# battery.net
KiCad netlist of a schematic drawn in Altium Designer
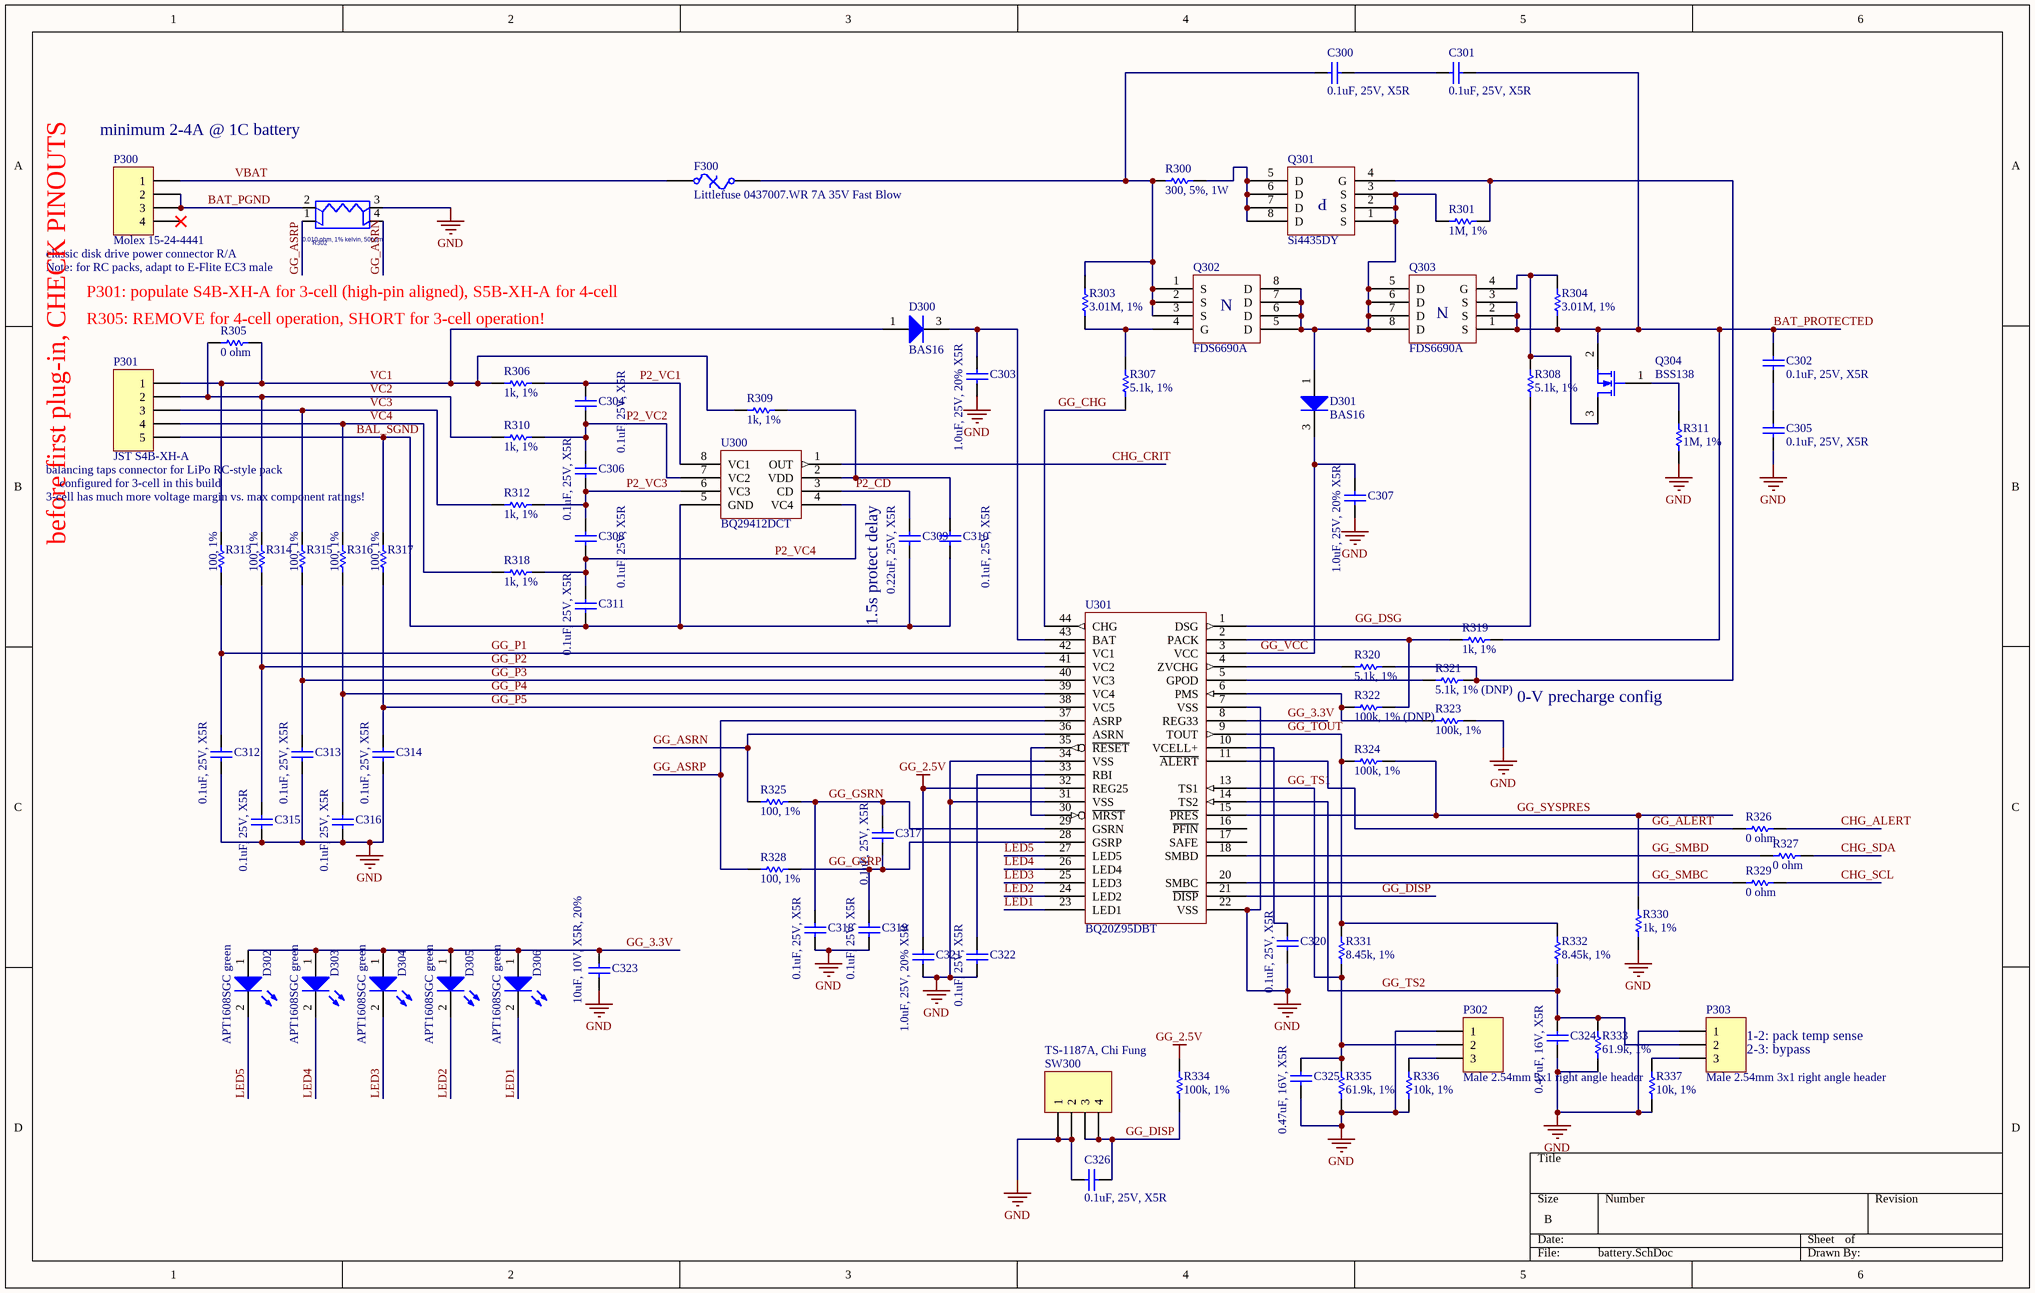
[diagram p0: battery.SchDoc]

(export (version "E")
  (design (tool "Eeschema 10.0.6"))
  (components
    (comp (ref "C300")
      (value "0.1uF, 25V, X5R")
      (footprint "CAPC1005N")
      (description "Capacitor (Semiconductor SIM Model)")
      (fields (field (name "PUBLISHER") "Altium Limited"))
      (libsource (lib "Miscellaneous Devices") (part "Cap Semi"))
    )
    (comp (ref "C301")
      (value "0.1uF, 25V, X5R")
      (footprint "CAPC1005N")
      (description "Capacitor (Semiconductor SIM Model)")
      (fields (field (name "PUBLISHER") "Altium Limited"))
      (libsource (lib "Miscellaneous Devices") (part "Cap Semi"))
    )
    (comp (ref "C302")
      (value "0.1uF, 25V, X5R")
      (footprint "CAPC1005N")
      (description "Capacitor (Semiconductor SIM Model)")
      (fields (field (name "PUBLISHER") "Altium Limited"))
      (libsource (lib "Miscellaneous Devices") (part "Cap Semi"))
    )
    (comp (ref "C303")
      (value "1.0uF, 25V, 20% X5R")
      (footprint "CAPC1608N")
      (description "Capacitor (Semiconductor SIM Model)")
      (fields (field (name "PUBLISHER") "Altium Limited"))
      (libsource (lib "Miscellaneous Devices") (part "Cap Semi"))
    )
    (comp (ref "C304")
      (value "0.1uF, 25V, X5R")
      (footprint "CAPC1005N")
      (description "Capacitor (Semiconductor SIM Model)")
      (fields (field (name "PUBLISHER") "Altium Limited"))
      (libsource (lib "Miscellaneous Devices") (part "Cap Semi"))
    )
    (comp (ref "C305")
      (value "0.1uF, 25V, X5R")
      (footprint "CAPC1005N")
      (description "Capacitor (Semiconductor SIM Model)")
      (fields (field (name "PUBLISHER") "Altium Limited"))
      (libsource (lib "Miscellaneous Devices") (part "Cap Semi"))
    )
    (comp (ref "C306")
      (value "0.1uF, 25V, X5R")
      (footprint "CAPC1005N")
      (description "Capacitor (Semiconductor SIM Model)")
      (fields (field (name "PUBLISHER") "Altium Limited"))
      (libsource (lib "Miscellaneous Devices") (part "Cap Semi"))
    )
    (comp (ref "C307")
      (value "1.0uF, 25V, 20% X5R")
      (footprint "CAPC1608N")
      (description "Capacitor (Semiconductor SIM Model)")
      (fields (field (name "PUBLISHER") "Altium Limited"))
      (libsource (lib "Miscellaneous Devices") (part "Cap Semi"))
    )
    (comp (ref "C308")
      (value "0.1uF, 25V, X5R")
      (footprint "CAPC1005N")
      (description "Capacitor (Semiconductor SIM Model)")
      (fields (field (name "PUBLISHER") "Altium Limited"))
      (libsource (lib "Miscellaneous Devices") (part "Cap Semi"))
    )
    (comp (ref "C309")
      (value "0.22uF, 25V, X5R")
      (footprint "CAPC1005N")
      (description "Capacitor (Semiconductor SIM Model)")
      (fields (field (name "PUBLISHER") "Altium Limited"))
      (libsource (lib "Miscellaneous Devices") (part "Cap Semi"))
    )
    (comp (ref "C310")
      (value "0.1uF, 25V, X5R")
      (footprint "CAPC1005N")
      (description "Capacitor (Semiconductor SIM Model)")
      (fields (field (name "PUBLISHER") "Altium Limited"))
      (libsource (lib "Miscellaneous Devices") (part "Cap Semi"))
    )
    (comp (ref "C311")
      (value "0.1uF, 25V, X5R")
      (footprint "CAPC1005N")
      (description "Capacitor (Semiconductor SIM Model)")
      (fields (field (name "PUBLISHER") "Altium Limited"))
      (libsource (lib "Miscellaneous Devices") (part "Cap Semi"))
    )
    (comp (ref "C312")
      (value "0.1uF, 25V, X5R")
      (footprint "CAPC1005N")
      (description "Capacitor (Semiconductor SIM Model)")
      (fields (field (name "PUBLISHER") "Altium Limited"))
      (libsource (lib "Miscellaneous Devices") (part "Cap Semi"))
    )
    (comp (ref "C313")
      (value "0.1uF, 25V, X5R")
      (footprint "CAPC1005N")
      (description "Capacitor (Semiconductor SIM Model)")
      (fields (field (name "PUBLISHER") "Altium Limited"))
      (libsource (lib "Miscellaneous Devices") (part "Cap Semi"))
    )
    (comp (ref "C314")
      (value "0.1uF, 25V, X5R")
      (footprint "CAPC1005N")
      (description "Capacitor (Semiconductor SIM Model)")
      (fields (field (name "PUBLISHER") "Altium Limited"))
      (libsource (lib "Miscellaneous Devices") (part "Cap Semi"))
    )
    (comp (ref "C315")
      (value "0.1uF, 25V, X5R")
      (footprint "CAPC1005N")
      (description "Capacitor (Semiconductor SIM Model)")
      (fields (field (name "PUBLISHER") "Altium Limited"))
      (libsource (lib "Miscellaneous Devices") (part "Cap Semi"))
    )
    (comp (ref "C316")
      (value "0.1uF, 25V, X5R")
      (footprint "CAPC1005N")
      (description "Capacitor (Semiconductor SIM Model)")
      (fields (field (name "PUBLISHER") "Altium Limited"))
      (libsource (lib "Miscellaneous Devices") (part "Cap Semi"))
    )
    (comp (ref "C317")
      (value "0.1uF, 25V, X5R")
      (footprint "CAPC1005N")
      (description "Capacitor (Semiconductor SIM Model)")
      (fields (field (name "PUBLISHER") "Altium Limited"))
      (libsource (lib "Miscellaneous Devices") (part "Cap Semi"))
    )
    (comp (ref "C318")
      (value "0.1uF, 25V, X5R")
      (footprint "CAPC1005N")
      (description "Capacitor (Semiconductor SIM Model)")
      (fields (field (name "PUBLISHER") "Altium Limited"))
      (libsource (lib "Miscellaneous Devices") (part "Cap Semi"))
    )
    (comp (ref "C319")
      (value "0.1uF, 25V, X5R")
      (footprint "CAPC1005N")
      (description "Capacitor (Semiconductor SIM Model)")
      (fields (field (name "PUBLISHER") "Altium Limited"))
      (libsource (lib "Miscellaneous Devices") (part "Cap Semi"))
    )
    (comp (ref "C320")
      (value "0.1uF, 25V, X5R")
      (footprint "CAPC1005N")
      (description "Capacitor (Semiconductor SIM Model)")
      (fields (field (name "PUBLISHER") "Altium Limited"))
      (libsource (lib "Miscellaneous Devices") (part "Cap Semi"))
    )
    (comp (ref "C321")
      (value "1.0uF, 25V, 20% X5R")
      (footprint "CAPC1608N")
      (description "Capacitor (Semiconductor SIM Model)")
      (fields (field (name "PUBLISHER") "Altium Limited"))
      (libsource (lib "Miscellaneous Devices") (part "Cap Semi"))
    )
    (comp (ref "C322")
      (value "0.1uF, 25V, X5R")
      (footprint "CAPC1005N")
      (description "Capacitor (Semiconductor SIM Model)")
      (fields (field (name "PUBLISHER") "Altium Limited"))
      (libsource (lib "Miscellaneous Devices") (part "Cap Semi"))
    )
    (comp (ref "C323")
      (value "10uF, 10V, X5R, 20%")
      (footprint "CAPC1608N")
      (description "Capacitor (Semiconductor SIM Model)")
      (fields (field (name "PUBLISHER") "Altium Limited"))
      (libsource (lib "Miscellaneous Devices") (part "Cap Semi"))
    )
    (comp (ref "C324")
      (value "0.47uF, 16V, X5R")
      (footprint "CAPC1005N")
      (description "Capacitor (Semiconductor SIM Model)")
      (fields (field (name "PUBLISHER") "Altium Limited"))
      (libsource (lib "Miscellaneous Devices") (part "Cap Semi"))
    )
    (comp (ref "C325")
      (value "0.47uF, 16V, X5R")
      (footprint "CAPC1005N")
      (description "Capacitor (Semiconductor SIM Model)")
      (fields (field (name "PUBLISHER") "Altium Limited"))
      (libsource (lib "Miscellaneous Devices") (part "Cap Semi"))
    )
    (comp (ref "C326")
      (value "0.1uF, 25V, X5R")
      (footprint "CAPC1005N")
      (description "Capacitor (Semiconductor SIM Model)")
      (fields (field (name "PUBLISHER") "Altium Limited"))
      (libsource (lib "Miscellaneous Devices") (part "Cap Semi"))
    )
    (comp (ref "D300")
      (value "BAS16")
      (footprint "SOT23-3N")
      (description "Silicon diode")
      (fields (field (name "PUBLISHER") "Altium Limited"))
      (libsource (lib "Miscellaneous Devices") (part "Diode 1N4148"))
    )
    (comp (ref "D301")
      (value "BAS16")
      (footprint "SOT23-3N")
      (description "Silicon diode")
      (fields (field (name "PUBLISHER") "Altium Limited"))
      (libsource (lib "Miscellaneous Devices") (part "Diode 1N4148"))
    )
    (comp (ref "D302")
      (value "APT1608SGC green")
      (footprint "CD1608-0603")
      (description "Typical RED, GREEN, YELLOW, AMBER GaAs LED")
      (fields (field (name "PUBLISHER") "Altium Limited"))
      (libsource (lib "Miscellaneous Devices") (part "LED2"))
    )
    (comp (ref "D303")
      (value "APT1608SGC green")
      (footprint "CD1608-0603")
      (description "Typical RED, GREEN, YELLOW, AMBER GaAs LED")
      (fields (field (name "PUBLISHER") "Altium Limited"))
      (libsource (lib "Miscellaneous Devices") (part "LED2"))
    )
    (comp (ref "D304")
      (value "APT1608SGC green")
      (footprint "CD1608-0603")
      (description "Typical RED, GREEN, YELLOW, AMBER GaAs LED")
      (fields (field (name "PUBLISHER") "Altium Limited"))
      (libsource (lib "Miscellaneous Devices") (part "LED2"))
    )
    (comp (ref "D305")
      (value "APT1608SGC green")
      (footprint "CD1608-0603")
      (description "Typical RED, GREEN, YELLOW, AMBER GaAs LED")
      (fields (field (name "PUBLISHER") "Altium Limited"))
      (libsource (lib "Miscellaneous Devices") (part "LED2"))
    )
    (comp (ref "D306")
      (value "APT1608SGC green")
      (footprint "CD1608-0603")
      (description "Typical RED, GREEN, YELLOW, AMBER GaAs LED")
      (fields (field (name "PUBLISHER") "Altium Limited"))
      (libsource (lib "Miscellaneous Devices") (part "LED2"))
    )
    (comp (ref "F300")
      (value "Littlefuse 0437007.WR 7A 35V Fast Blow")
      (footprint "RESC3216N")
      (description "Thermal Fuse")
      (fields (field (name "PUBLISHER") "Altium Limited"))
      (libsource (lib "Miscellaneous Devices") (part "Fuse Thermal"))
    )
    (comp (ref "P300")
      (value "Molex 15-24-4441")
      (footprint "MOLEX_15-24-4441")
      (description "Classic PC hard drive power connector, RA")
      (fields (field (name "PUBLISHER") "Altium Limited"))
      (libsource (lib "Miscellaneous Connectors") (part "Header 4"))
    )
    (comp (ref "P301")
      (value "JST S4B-XH-A")
      (footprint "JST_S5B-XH-A_OPT4")
      (description "JST S4B-XH-A 2.5mm RA connector, stuffed in 5-pin slot, high pin aligned")
      (fields (field (name "PUBLISHER") "Altium Limited"))
      (libsource (lib "Miscellaneous Connectors") (part "Header 5"))
    )
    (comp (ref "P302")
      (value "Male 2.54mm 3x1 right angle header")
      (footprint "HDR1X3H")
      (description "Header, 3-Pin, Right Angle")
      (fields (field (name "PUBLISHER") "Altium Limited"))
      (libsource (lib "Miscellaneous Connectors") (part "Header 3H"))
    )
    (comp (ref "P303")
      (value "Male 2.54mm 3x1 right angle header")
      (footprint "HDR1X3H")
      (description "Header, 3-Pin, Right Angle")
      (fields (field (name "PUBLISHER") "Altium Limited"))
      (libsource (lib "Miscellaneous Connectors") (part "Header 3H"))
    )
    (comp (ref "Q301")
      (value "Si4435DY")
      (footprint "SOIC127P600-8AN")
      (description "Singre P-channel FET, 8A, 30V")
      (libsource (lib "commonsch") (part "Si4435DY"))
    )
    (comp (ref "Q302")
      (value "FDS6690A")
      (footprint "SOIC127P600-8AN")
      (description "Single N-channel FET, 11A, 30V")
      (libsource (lib "commonsch") (part "FDS6690A"))
    )
    (comp (ref "Q303")
      (value "FDS6690A")
      (footprint "SOIC127P600-8AN")
      (description "Single N-channel FET, 11A, 30V")
      (libsource (lib "") (part "FDS6690A_1"))
    )
    (comp (ref "Q304")
      (value "BSS138")
      (footprint "SOT23-3N")
      (description "N-Channel MOSFET")
      (fields (field (name "PUBLISHER") "Altium Limited"))
      (libsource (lib "Miscellaneous Devices") (part "MOSFET-N"))
    )
    (comp (ref "R300")
      (value "300, 5%, 1W")
      (footprint "RESC6432N")
      (description "Resistor")
      (fields (field (name "PUBLISHER") "Altium Limited"))
      (libsource (lib "Miscellaneous Devices") (part "Res1"))
    )
    (comp (ref "R301")
      (value "1M, 1%")
      (footprint "RESC1005N")
      (description "Resistor")
      (fields (field (name "PUBLISHER") "Altium Limited"))
      (libsource (lib "Miscellaneous Devices") (part "Res1"))
    )
    (comp (ref "R302")
      (value "0.010 ohm, 1% kelvin, 50ppm")
      (fields
        (field (name "PART_NUMBER") "R00034-001")
        (field (name "TOLERANCE") "?")
        (field (name "MFG") "OHMITE")
      )
      (libsource (lib "*") (part "RES_4TERM"))
    )
    (comp (ref "R303")
      (value "3.01M, 1%")
      (footprint "RESC1005N")
      (description "Resistor")
      (fields (field (name "PUBLISHER") "Altium Limited"))
      (libsource (lib "Miscellaneous Devices") (part "Res1"))
    )
    (comp (ref "R304")
      (value "3.01M, 1%")
      (footprint "RESC1005N")
      (description "Resistor")
      (fields (field (name "PUBLISHER") "Altium Limited"))
      (libsource (lib "Miscellaneous Devices") (part "Res1"))
    )
    (comp (ref "R305")
      (value "0 ohm")
      (footprint "RESC1005N")
      (description "Resistor")
      (fields (field (name "PUBLISHER") "Altium Limited"))
      (libsource (lib "Miscellaneous Devices") (part "Res1"))
    )
    (comp (ref "R306")
      (value "1k, 1%")
      (footprint "RESC1005N")
      (description "Resistor")
      (fields (field (name "PUBLISHER") "Altium Limited"))
      (libsource (lib "Miscellaneous Devices") (part "Res1"))
    )
    (comp (ref "R307")
      (value "5.1k, 1%")
      (footprint "RESC1005N")
      (description "Resistor")
      (fields (field (name "PUBLISHER") "Altium Limited"))
      (libsource (lib "Miscellaneous Devices") (part "Res1"))
    )
    (comp (ref "R308")
      (value "5.1k, 1%")
      (footprint "RESC1005N")
      (description "Resistor")
      (fields (field (name "PUBLISHER") "Altium Limited"))
      (libsource (lib "Miscellaneous Devices") (part "Res1"))
    )
    (comp (ref "R309")
      (value "1k, 1%")
      (footprint "RESC1005N")
      (description "Resistor")
      (fields (field (name "PUBLISHER") "Altium Limited"))
      (libsource (lib "Miscellaneous Devices") (part "Res1"))
    )
    (comp (ref "R310")
      (value "1k, 1%")
      (footprint "RESC1005N")
      (description "Resistor")
      (fields (field (name "PUBLISHER") "Altium Limited"))
      (libsource (lib "Miscellaneous Devices") (part "Res1"))
    )
    (comp (ref "R311")
      (value "1M, 1%")
      (footprint "RESC1005N")
      (description "Resistor")
      (fields (field (name "PUBLISHER") "Altium Limited"))
      (libsource (lib "Miscellaneous Devices") (part "Res1"))
    )
    (comp (ref "R312")
      (value "1k, 1%")
      (footprint "RESC1005N")
      (description "Resistor")
      (fields (field (name "PUBLISHER") "Altium Limited"))
      (libsource (lib "Miscellaneous Devices") (part "Res1"))
    )
    (comp (ref "R313")
      (value "100, 1%")
      (footprint "RESC1005N")
      (description "Resistor")
      (fields (field (name "PUBLISHER") "Altium Limited"))
      (libsource (lib "Miscellaneous Devices") (part "Res1"))
    )
    (comp (ref "R314")
      (value "100, 1%")
      (footprint "RESC1005N")
      (description "Resistor")
      (fields (field (name "PUBLISHER") "Altium Limited"))
      (libsource (lib "Miscellaneous Devices") (part "Res1"))
    )
    (comp (ref "R315")
      (value "100, 1%")
      (footprint "RESC1005N")
      (description "Resistor")
      (fields (field (name "PUBLISHER") "Altium Limited"))
      (libsource (lib "Miscellaneous Devices") (part "Res1"))
    )
    (comp (ref "R316")
      (value "100, 1%")
      (footprint "RESC1005N")
      (description "Resistor")
      (fields (field (name "PUBLISHER") "Altium Limited"))
      (libsource (lib "Miscellaneous Devices") (part "Res1"))
    )
    (comp (ref "R317")
      (value "100, 1%")
      (footprint "RESC1005N")
      (description "Resistor")
      (fields (field (name "PUBLISHER") "Altium Limited"))
      (libsource (lib "Miscellaneous Devices") (part "Res1"))
    )
    (comp (ref "R318")
      (value "1k, 1%")
      (footprint "RESC1005N")
      (description "Resistor")
      (fields (field (name "PUBLISHER") "Altium Limited"))
      (libsource (lib "Miscellaneous Devices") (part "Res1"))
    )
    (comp (ref "R319")
      (value "1k, 1%")
      (footprint "RESC1005N")
      (description "Resistor")
      (fields (field (name "PUBLISHER") "Altium Limited"))
      (libsource (lib "Miscellaneous Devices") (part "Res1"))
    )
    (comp (ref "R320")
      (value "5.1k, 1%")
      (footprint "RESC1005N")
      (description "Resistor")
      (fields (field (name "PUBLISHER") "Altium Limited"))
      (libsource (lib "Miscellaneous Devices") (part "Res1"))
    )
    (comp (ref "R321")
      (value "5.1k, 1% (DNP)")
      (footprint "RESC1005N")
      (description "Resistor")
      (fields (field (name "PUBLISHER") "Altium Limited"))
      (libsource (lib "Miscellaneous Devices") (part "Res1"))
    )
    (comp (ref "R322")
      (value "100k, 1% (DNP)")
      (footprint "RESC1005N")
      (description "Resistor")
      (fields (field (name "PUBLISHER") "Altium Limited"))
      (libsource (lib "Miscellaneous Devices") (part "Res1"))
    )
    (comp (ref "R323")
      (value "100k, 1%")
      (footprint "RESC1005N")
      (description "Resistor")
      (fields (field (name "PUBLISHER") "Altium Limited"))
      (libsource (lib "Miscellaneous Devices") (part "Res1"))
    )
    (comp (ref "R324")
      (value "100k, 1%")
      (footprint "RESC1005N")
      (description "Resistor")
      (fields (field (name "PUBLISHER") "Altium Limited"))
      (libsource (lib "Miscellaneous Devices") (part "Res1"))
    )
    (comp (ref "R325")
      (value "100, 1%")
      (footprint "RESC1005N")
      (description "Resistor")
      (fields (field (name "PUBLISHER") "Altium Limited"))
      (libsource (lib "Miscellaneous Devices") (part "Res1"))
    )
    (comp (ref "R326")
      (value "0 ohm")
      (footprint "RESC1005N")
      (description "Resistor")
      (fields (field (name "PUBLISHER") "Altium Limited"))
      (libsource (lib "Miscellaneous Devices") (part "Res1"))
    )
    (comp (ref "R327")
      (value "0 ohm")
      (footprint "RESC1005N")
      (description "Resistor")
      (fields (field (name "PUBLISHER") "Altium Limited"))
      (libsource (lib "Miscellaneous Devices") (part "Res1"))
    )
    (comp (ref "R328")
      (value "100, 1%")
      (footprint "RESC1005N")
      (description "Resistor")
      (fields (field (name "PUBLISHER") "Altium Limited"))
      (libsource (lib "Miscellaneous Devices") (part "Res1"))
    )
    (comp (ref "R329")
      (value "0 ohm")
      (footprint "RESC1005N")
      (description "Resistor")
      (fields (field (name "PUBLISHER") "Altium Limited"))
      (libsource (lib "Miscellaneous Devices") (part "Res1"))
    )
    (comp (ref "R330")
      (value "1k, 1%")
      (footprint "RESC1005N")
      (description "Resistor")
      (fields (field (name "PUBLISHER") "Altium Limited"))
      (libsource (lib "Miscellaneous Devices") (part "Res1"))
    )
    (comp (ref "R331")
      (value "8.45k, 1%")
      (footprint "RESC1005N")
      (description "Resistor")
      (fields (field (name "PUBLISHER") "Altium Limited"))
      (libsource (lib "Miscellaneous Devices") (part "Res1"))
    )
    (comp (ref "R332")
      (value "8.45k, 1%")
      (footprint "RESC1005N")
      (description "Resistor")
      (fields (field (name "PUBLISHER") "Altium Limited"))
      (libsource (lib "Miscellaneous Devices") (part "Res1"))
    )
    (comp (ref "R333")
      (value "61.9k, 1%")
      (footprint "RESC1005N")
      (description "Resistor")
      (fields (field (name "PUBLISHER") "Altium Limited"))
      (libsource (lib "Miscellaneous Devices") (part "Res1"))
    )
    (comp (ref "R334")
      (value "100k, 1%")
      (footprint "RESC1005N")
      (description "Resistor")
      (fields (field (name "PUBLISHER") "Altium Limited"))
      (libsource (lib "Miscellaneous Devices") (part "Res1"))
    )
    (comp (ref "R335")
      (value "61.9k, 1%")
      (footprint "RESC1005N")
      (description "Resistor")
      (fields (field (name "PUBLISHER") "Altium Limited"))
      (libsource (lib "Miscellaneous Devices") (part "Res1"))
    )
    (comp (ref "R336")
      (value "10k, 1%")
      (footprint "RESC1005N")
      (description "Resistor")
      (fields (field (name "PUBLISHER") "Altium Limited"))
      (libsource (lib "Miscellaneous Devices") (part "Res1"))
    )
    (comp (ref "R337")
      (value "10k, 1%")
      (footprint "RESC1005N")
      (description "Resistor")
      (fields (field (name "PUBLISHER") "Altium Limited"))
      (libsource (lib "Miscellaneous Devices") (part "Res1"))
    )
    (comp (ref "SW300")
      (value "TS-1187A, Chi Fung")
      (footprint "SWITCH_TS-1187A")
      (description "Chi Fung TS-1187A")
      (fields (field (name "PUBLISHER") "Altium Limited"))
      (libsource (lib "") (part "Header 4_1"))
    )
    (comp (ref "U300")
      (value "BQ29412DCT")
      (footprint "TSOP65P490-8AN")
      (description "Voltage protection for 2-,3-, and 4-cell LiIon batteries (2nd level)")
      (libsource (lib "commonsch") (part "BQ2941XDCT"))
    )
    (comp (ref "U301")
      (value "BQ20Z95DBT")
      (footprint "TSSOP50P640-44N")
      (description "SBS 1.1-Compliant Gas Gauge and Protection with Impedance Track (TM)")
      (libsource (lib "commonsch") (part "BQ20Z95DBT"))
    )
  )
  (nets
    (net (code "1") (name "/BAL_SGND") (class "Default")
      (node (ref "C309") (pin "2") (pinfunction "2_2") (pintype "passive"))
      (node (ref "C310") (pin "2") (pinfunction "2_2") (pintype "passive"))
      (node (ref "C311") (pin "2") (pinfunction "2_2") (pintype "passive"))
      (node (ref "P301") (pin "5") (pinfunction "5_5") (pintype "passive"))
      (node (ref "R317") (pin "1") (pinfunction "1_1") (pintype "passive"))
      (node (ref "U300") (pin "5") (pinfunction "GND_5") (pintype "power_in"))
    )
    (net (code "2") (name "/BAT_PGND") (class "Default")
      (node (ref "P300") (pin "2") (pinfunction "2_2") (pintype "passive"))
      (node (ref "P300") (pin "3") (pinfunction "3_3") (pintype "passive"))
      (node (ref "R302") (pin "2") (pinfunction "2_2") (pintype "bidirectional"))
    )
    (net (code "3") (name "/BAT_PROTECTED") (class "Default")
      (node (ref "C301") (pin "1") (pinfunction "1_1") (pintype "passive"))
      (node (ref "C302") (pin "2") (pinfunction "2_2") (pintype "passive"))
      (node (ref "Q303") (pin "1") (pinfunction "S_1") (pintype "passive"))
      (node (ref "Q303") (pin "2") (pinfunction "S_2") (pintype "passive"))
      (node (ref "Q303") (pin "3") (pinfunction "S_3") (pintype "passive"))
      (node (ref "Q304") (pin "2") (pinfunction "S_2") (pintype "passive"))
      (node (ref "R304") (pin "2") (pinfunction "2_2") (pintype "passive"))
      (node (ref "R319") (pin "1") (pinfunction "1_1") (pintype "passive"))
    )
    (net (code "4") (name "/CHG_ALERT") (class "Default")
      (node (ref "R326") (pin "2") (pinfunction "2_2") (pintype "passive"))
    )
    (net (code "5") (name "/CHG_CRIT") (class "Default")
      (node (ref "U300") (pin "1") (pinfunction "OUT_1") (pintype "output"))
    )
    (net (code "6") (name "/CHG_SCL") (class "Default")
      (node (ref "R329") (pin "2") (pinfunction "2_2") (pintype "passive"))
    )
    (net (code "7") (name "/CHG_SDA") (class "Default")
      (node (ref "R327") (pin "2") (pinfunction "2_2") (pintype "passive"))
    )
    (net (code "8") (name "/GG_3.3V") (class "Default")
      (node (ref "C323") (pin "1") (pinfunction "1_1") (pintype "passive"))
      (node (ref "D302") (pin "1") (pinfunction "A_1") (pintype "passive"))
      (node (ref "D303") (pin "1") (pinfunction "A_1") (pintype "passive"))
      (node (ref "D304") (pin "1") (pinfunction "A_1") (pintype "passive"))
      (node (ref "D305") (pin "1") (pinfunction "A_1") (pintype "passive"))
      (node (ref "D306") (pin "1") (pinfunction "A_1") (pintype "passive"))
      (node (ref "U301") (pin "8") (pinfunction "REG33_8") (pintype "power_in"))
    )
    (net (code "9") (name "/GG_ALERT") (class "Default")
      (node (ref "R326") (pin "1") (pinfunction "1_1") (pintype "passive"))
      (node (ref "U301") (pin "11") (pinfunction "~{ALERT}_11") (pintype "open_collector"))
    )
    (net (code "10") (name "/GG_ASRN") (class "Default")
      (node (ref "R302") (pin "4") (pinfunction "4_4") (pintype "bidirectional"))
      (node (ref "R325") (pin "2") (pinfunction "2_2") (pintype "passive"))
      (node (ref "U301") (pin "36") (pinfunction "ASRN_36") (pintype "passive"))
    )
    (net (code "11") (name "/GG_ASRP") (class "Default")
      (node (ref "R302") (pin "1") (pinfunction "1_1") (pintype "bidirectional"))
      (node (ref "R328") (pin "2") (pinfunction "2_2") (pintype "passive"))
      (node (ref "U301") (pin "37") (pinfunction "ASRP_37") (pintype "passive"))
    )
    (net (code "12") (name "/GG_CHG") (class "Default")
      (node (ref "R307") (pin "2") (pinfunction "2_2") (pintype "passive"))
      (node (ref "U301") (pin "44") (pinfunction "CHG_44") (pintype "output"))
    )
    (net (code "13") (name "/GG_DISP") (class "Default")
      (node (ref "C326") (pin "1") (pinfunction "1_1") (pintype "passive"))
      (node (ref "R334") (pin "1") (pinfunction "1_1") (pintype "passive"))
      (node (ref "SW300") (pin "3") (pinfunction "3_3") (pintype "passive"))
      (node (ref "SW300") (pin "4") (pinfunction "4_4") (pintype "passive"))
      (node (ref "U301") (pin "21") (pinfunction "~{DISP}_21") (pintype "open_collector"))
    )
    (net (code "14") (name "/GG_DSG") (class "Default")
      (node (ref "R308") (pin "2") (pinfunction "2_2") (pintype "passive"))
      (node (ref "U301") (pin "1") (pinfunction "DSG_1") (pintype "output"))
    )
    (net (code "15") (name "/GG_GSRN") (class "Default")
      (node (ref "C317") (pin "1") (pinfunction "1_1") (pintype "passive"))
      (node (ref "C318") (pin "1") (pinfunction "1_1") (pintype "passive"))
      (node (ref "R325") (pin "1") (pinfunction "1_1") (pintype "passive"))
      (node (ref "U301") (pin "29") (pinfunction "GSRN_29") (pintype "passive"))
    )
    (net (code "16") (name "/GG_GSRP") (class "Default")
      (node (ref "C317") (pin "2") (pinfunction "2_2") (pintype "passive"))
      (node (ref "C319") (pin "1") (pinfunction "1_1") (pintype "passive"))
      (node (ref "R328") (pin "1") (pinfunction "1_1") (pintype "passive"))
      (node (ref "U301") (pin "28") (pinfunction "GSRP_28") (pintype "passive"))
    )
    (net (code "17") (name "/GG_P1") (class "Default")
      (node (ref "C312") (pin "1") (pinfunction "1_1") (pintype "passive"))
      (node (ref "R313") (pin "2") (pinfunction "2_2") (pintype "passive"))
      (node (ref "U301") (pin "42") (pinfunction "VC1_42") (pintype "passive"))
    )
    (net (code "18") (name "/GG_P2") (class "Default")
      (node (ref "C315") (pin "1") (pinfunction "1_1") (pintype "passive"))
      (node (ref "R314") (pin "2") (pinfunction "2_2") (pintype "passive"))
      (node (ref "U301") (pin "41") (pinfunction "VC2_41") (pintype "passive"))
    )
    (net (code "19") (name "/GG_P3") (class "Default")
      (node (ref "C313") (pin "1") (pinfunction "1_1") (pintype "passive"))
      (node (ref "R315") (pin "2") (pinfunction "2_2") (pintype "passive"))
      (node (ref "U301") (pin "40") (pinfunction "VC3_40") (pintype "passive"))
    )
    (net (code "20") (name "/GG_P4") (class "Default")
      (node (ref "C316") (pin "1") (pinfunction "1_1") (pintype "passive"))
      (node (ref "R316") (pin "2") (pinfunction "2_2") (pintype "passive"))
      (node (ref "U301") (pin "39") (pinfunction "VC4_39") (pintype "passive"))
    )
    (net (code "21") (name "/GG_P5") (class "Default")
      (node (ref "C314") (pin "1") (pinfunction "1_1") (pintype "passive"))
      (node (ref "R317") (pin "2") (pinfunction "2_2") (pintype "passive"))
      (node (ref "U301") (pin "38") (pinfunction "VC5_38") (pintype "passive"))
    )
    (net (code "22") (name "/GG_SMBC") (class "Default")
      (node (ref "R329") (pin "1") (pinfunction "1_1") (pintype "passive"))
      (node (ref "U301") (pin "20") (pinfunction "SMBC_20") (pintype "open_collector"))
    )
    (net (code "23") (name "/GG_SMBD") (class "Default")
      (node (ref "R327") (pin "1") (pinfunction "1_1") (pintype "passive"))
      (node (ref "U301") (pin "18") (pinfunction "SMBD_18") (pintype "open_collector"))
    )
    (net (code "24") (name "/GG_SYSPRES") (class "Default")
      (node (ref "R324") (pin "2") (pinfunction "2_2") (pintype "passive"))
      (node (ref "R330") (pin "1") (pinfunction "1_1") (pintype "passive"))
      (node (ref "U301") (pin "15") (pinfunction "~{PRES}_15") (pintype "open_collector"))
    )
    (net (code "25") (name "/GG_TOUT") (class "Default")
      (node (ref "R324") (pin "1") (pinfunction "1_1") (pintype "passive"))
      (node (ref "R331") (pin "2") (pinfunction "2_2") (pintype "passive"))
      (node (ref "R332") (pin "2") (pinfunction "2_2") (pintype "passive"))
      (node (ref "U301") (pin "9") (pinfunction "TOUT_9") (pintype "output"))
    )
    (net (code "26") (name "/GG_TS1") (class "Default")
      (node (ref "C325") (pin "1") (pinfunction "1_1") (pintype "passive"))
      (node (ref "P302") (pin "2") (pinfunction "2_2") (pintype "passive"))
      (node (ref "R331") (pin "1") (pinfunction "1_1") (pintype "passive"))
      (node (ref "R335") (pin "2") (pinfunction "2_2") (pintype "passive"))
      (node (ref "U301") (pin "13") (pinfunction "TS1_13") (pintype "input"))
    )
    (net (code "27") (name "/GG_TS2") (class "Default")
      (node (ref "C324") (pin "1") (pinfunction "1_1") (pintype "passive"))
      (node (ref "P303") (pin "2") (pinfunction "2_2") (pintype "passive"))
      (node (ref "R332") (pin "1") (pinfunction "1_1") (pintype "passive"))
      (node (ref "R333") (pin "2") (pinfunction "2_2") (pintype "passive"))
      (node (ref "U301") (pin "14") (pinfunction "TS2_14") (pintype "input"))
    )
    (net (code "28") (name "/GG_VCC") (class "Default")
      (node (ref "C307") (pin "1") (pinfunction "1_1") (pintype "passive"))
      (node (ref "D301") (pin "3") (pinfunction "K_3") (pintype "passive"))
      (node (ref "U301") (pin "3") (pinfunction "VCC_3") (pintype "power_in"))
    )
    (net (code "29") (name "/LED1") (class "Default")
      (node (ref "D306") (pin "2") (pinfunction "K_2") (pintype "passive"))
      (node (ref "U301") (pin "23") (pinfunction "LED1_23") (pintype "passive"))
    )
    (net (code "30") (name "/LED2") (class "Default")
      (node (ref "D305") (pin "2") (pinfunction "K_2") (pintype "passive"))
      (node (ref "U301") (pin "24") (pinfunction "LED2_24") (pintype "passive"))
    )
    (net (code "31") (name "/LED3") (class "Default")
      (node (ref "D304") (pin "2") (pinfunction "K_2") (pintype "passive"))
      (node (ref "U301") (pin "25") (pinfunction "LED3_25") (pintype "passive"))
    )
    (net (code "32") (name "/LED4") (class "Default")
      (node (ref "D303") (pin "2") (pinfunction "K_2") (pintype "passive"))
      (node (ref "U301") (pin "26") (pinfunction "LED4_26") (pintype "passive"))
    )
    (net (code "33") (name "/LED5") (class "Default")
      (node (ref "D302") (pin "2") (pinfunction "K_2") (pintype "passive"))
      (node (ref "U301") (pin "27") (pinfunction "LED5_27") (pintype "passive"))
    )
    (net (code "34") (name "/P2_CD") (class "Default")
      (node (ref "C309") (pin "1") (pinfunction "1_1") (pintype "passive"))
      (node (ref "U300") (pin "3") (pinfunction "CD_3") (pintype "passive"))
    )
    (net (code "35") (name "/P2_VC1") (class "Default")
      (node (ref "C304") (pin "1") (pinfunction "1_1") (pintype "passive"))
      (node (ref "R306") (pin "2") (pinfunction "2_2") (pintype "passive"))
      (node (ref "U300") (pin "8") (pinfunction "VC1_8") (pintype "passive"))
    )
    (net (code "36") (name "/P2_VC2") (class "Default")
      (node (ref "C304") (pin "2") (pinfunction "2_2") (pintype "passive"))
      (node (ref "C306") (pin "1") (pinfunction "1_1") (pintype "passive"))
      (node (ref "R310") (pin "2") (pinfunction "2_2") (pintype "passive"))
      (node (ref "U300") (pin "7") (pinfunction "VC2_7") (pintype "passive"))
    )
    (net (code "37") (name "/P2_VC3") (class "Default")
      (node (ref "C306") (pin "2") (pinfunction "2_2") (pintype "passive"))
      (node (ref "C308") (pin "1") (pinfunction "1_1") (pintype "passive"))
      (node (ref "R312") (pin "2") (pinfunction "2_2") (pintype "passive"))
      (node (ref "U300") (pin "6") (pinfunction "VC3_6") (pintype "passive"))
    )
    (net (code "38") (name "/P2_VC4") (class "Default")
      (node (ref "C308") (pin "2") (pinfunction "2_2") (pintype "passive"))
      (node (ref "C311") (pin "1") (pinfunction "1_1") (pintype "passive"))
      (node (ref "R318") (pin "2") (pinfunction "2_2") (pintype "passive"))
      (node (ref "U300") (pin "4") (pinfunction "VC4_4") (pintype "passive"))
    )
    (net (code "39") (name "/VBAT") (class "Default")
      (node (ref "F300") (pin "1") (pinfunction "1_1") (pintype "passive"))
      (node (ref "P300") (pin "1") (pinfunction "1_1") (pintype "passive"))
    )
    (net (code "40") (name "/VC1") (class "Default")
      (node (ref "D300") (pin "1") (pinfunction "A_1") (pintype "passive"))
      (node (ref "P301") (pin "1") (pinfunction "1_1") (pintype "passive"))
      (node (ref "R305") (pin "2") (pinfunction "2_2") (pintype "passive"))
      (node (ref "R306") (pin "1") (pinfunction "1_1") (pintype "passive"))
      (node (ref "R309") (pin "1") (pinfunction "1_1") (pintype "passive"))
      (node (ref "R313") (pin "1") (pinfunction "1_1") (pintype "passive"))
    )
    (net (code "41") (name "/VC2") (class "Default")
      (node (ref "P301") (pin "2") (pinfunction "2_2") (pintype "passive"))
      (node (ref "R305") (pin "1") (pinfunction "1_1") (pintype "passive"))
      (node (ref "R310") (pin "1") (pinfunction "1_1") (pintype "passive"))
      (node (ref "R314") (pin "1") (pinfunction "1_1") (pintype "passive"))
    )
    (net (code "42") (name "/VC3") (class "Default")
      (node (ref "P301") (pin "3") (pinfunction "3_3") (pintype "passive"))
      (node (ref "R312") (pin "1") (pinfunction "1_1") (pintype "passive"))
      (node (ref "R315") (pin "1") (pinfunction "1_1") (pintype "passive"))
    )
    (net (code "43") (name "/VC4") (class "Default")
      (node (ref "P301") (pin "4") (pinfunction "4_4") (pintype "passive"))
      (node (ref "R316") (pin "1") (pinfunction "1_1") (pintype "passive"))
      (node (ref "R318") (pin "1") (pinfunction "1_1") (pintype "passive"))
    )
    (net (code "44") (name "GG_2.5V") (class "Default")
      (node (ref "C321") (pin "1") (pinfunction "1_1") (pintype "passive"))
      (node (ref "R334") (pin "2") (pinfunction "2_2") (pintype "passive"))
      (node (ref "U301") (pin "32") (pinfunction "REG25_32") (pintype "power_in"))
    )
    (net (code "45") (name "GND") (class "Default")
      (node (ref "C303") (pin "2") (pinfunction "2_2") (pintype "passive"))
      (node (ref "C305") (pin "1") (pinfunction "1_1") (pintype "passive"))
      (node (ref "C307") (pin "2") (pinfunction "2_2") (pintype "passive"))
      (node (ref "C312") (pin "2") (pinfunction "2_2") (pintype "passive"))
      (node (ref "C313") (pin "2") (pinfunction "2_2") (pintype "passive"))
      (node (ref "C314") (pin "2") (pinfunction "2_2") (pintype "passive"))
      (node (ref "C315") (pin "2") (pinfunction "2_2") (pintype "passive"))
      (node (ref "C316") (pin "2") (pinfunction "2_2") (pintype "passive"))
      (node (ref "C318") (pin "2") (pinfunction "2_2") (pintype "passive"))
      (node (ref "C319") (pin "2") (pinfunction "2_2") (pintype "passive"))
      (node (ref "C320") (pin "2") (pinfunction "2_2") (pintype "passive"))
      (node (ref "C321") (pin "2") (pinfunction "2_2") (pintype "passive"))
      (node (ref "C322") (pin "2") (pinfunction "2_2") (pintype "passive"))
      (node (ref "C323") (pin "2") (pinfunction "2_2") (pintype "passive"))
      (node (ref "C324") (pin "2") (pinfunction "2_2") (pintype "passive"))
      (node (ref "C325") (pin "2") (pinfunction "2_2") (pintype "passive"))
      (node (ref "C326") (pin "2") (pinfunction "2_2") (pintype "passive"))
      (node (ref "P302") (pin "1") (pinfunction "1_1") (pintype "passive"))
      (node (ref "P303") (pin "1") (pinfunction "1_1") (pintype "passive"))
      (node (ref "R302") (pin "3") (pinfunction "3_3") (pintype "bidirectional"))
      (node (ref "R311") (pin "2") (pinfunction "2_2") (pintype "passive"))
      (node (ref "R323") (pin "2") (pinfunction "2_2") (pintype "passive"))
      (node (ref "R330") (pin "2") (pinfunction "2_2") (pintype "passive"))
      (node (ref "R333") (pin "1") (pinfunction "1_1") (pintype "passive"))
      (node (ref "R335") (pin "1") (pinfunction "1_1") (pintype "passive"))
      (node (ref "R336") (pin "1") (pinfunction "1_1") (pintype "passive"))
      (node (ref "R337") (pin "1") (pinfunction "1_1") (pintype "passive"))
      (node (ref "SW300") (pin "1") (pinfunction "1_1") (pintype "passive"))
      (node (ref "SW300") (pin "2") (pinfunction "2_2") (pintype "passive"))
      (node (ref "U301") (pin "22") (pinfunction "VSS_22") (pintype "power_in"))
      (node (ref "U301") (pin "31") (pinfunction "VSS_31") (pintype "power_in"))
      (node (ref "U301") (pin "34") (pinfunction "VSS_34") (pintype "power_in"))
      (node (ref "U301") (pin "7") (pinfunction "VSS_7") (pintype "power_in"))
    )
    (net (code "46") (name "Net-(C300-Pad1)") (class "Default")
      (node (ref "C300") (pin "1") (pinfunction "1_1") (pintype "passive"))
      (node (ref "C301") (pin "2") (pinfunction "2_2") (pintype "passive"))
    )
    (net (code "47") (name "Net-(C300-Pad2)") (class "Default")
      (node (ref "C300") (pin "2") (pinfunction "2_2") (pintype "passive"))
      (node (ref "F300") (pin "2") (pinfunction "2_2") (pintype "passive"))
      (node (ref "Q302") (pin "1") (pinfunction "S_1") (pintype "passive"))
      (node (ref "Q302") (pin "2") (pinfunction "S_2") (pintype "passive"))
      (node (ref "Q302") (pin "3") (pinfunction "S_3") (pintype "passive"))
      (node (ref "R300") (pin "2") (pinfunction "2_2") (pintype "passive"))
      (node (ref "R303") (pin "1") (pinfunction "1_1") (pintype "passive"))
    )
    (net (code "48") (name "Net-(C302-Pad1)") (class "Default")
      (node (ref "C302") (pin "1") (pinfunction "1_1") (pintype "passive"))
      (node (ref "C305") (pin "2") (pinfunction "2_2") (pintype "passive"))
    )
    (net (code "49") (name "Net-(D300-K)") (class "Default")
      (node (ref "C303") (pin "1") (pinfunction "1_1") (pintype "passive"))
      (node (ref "D300") (pin "3") (pinfunction "K_3") (pintype "passive"))
      (node (ref "U301") (pin "43") (pinfunction "BAT_43") (pintype "passive"))
    )
    (net (code "50") (name "Net-(D301-A)") (class "Default")
      (node (ref "D301") (pin "1") (pinfunction "A_1") (pintype "passive"))
      (node (ref "Q301") (pin "1") (pinfunction "S_1") (pintype "passive"))
      (node (ref "Q301") (pin "2") (pinfunction "S_2") (pintype "passive"))
      (node (ref "Q301") (pin "3") (pinfunction "S_3") (pintype "passive"))
      (node (ref "Q302") (pin "5") (pinfunction "D_5") (pintype "passive"))
      (node (ref "Q302") (pin "6") (pinfunction "D_6") (pintype "passive"))
      (node (ref "Q302") (pin "7") (pinfunction "D_7") (pintype "passive"))
      (node (ref "Q302") (pin "8") (pinfunction "D_8") (pintype "passive"))
      (node (ref "Q303") (pin "5") (pinfunction "D_5") (pintype "passive"))
      (node (ref "Q303") (pin "6") (pinfunction "D_6") (pintype "passive"))
      (node (ref "Q303") (pin "7") (pinfunction "D_7") (pintype "passive"))
      (node (ref "Q303") (pin "8") (pinfunction "D_8") (pintype "passive"))
      (node (ref "R301") (pin "2") (pinfunction "2_2") (pintype "passive"))
    )
    (net (code "51") (name "Net-(P302-Pad3)") (class "Default")
      (node (ref "P302") (pin "3") (pinfunction "3_3") (pintype "passive"))
      (node (ref "R336") (pin "2") (pinfunction "2_2") (pintype "passive"))
    )
    (net (code "52") (name "Net-(P303-Pad3)") (class "Default")
      (node (ref "P303") (pin "3") (pinfunction "3_3") (pintype "passive"))
      (node (ref "R337") (pin "2") (pinfunction "2_2") (pintype "passive"))
    )
    (net (code "53") (name "Net-(Q301-D-Pad5)") (class "Default")
      (node (ref "Q301") (pin "5") (pinfunction "D_5") (pintype "passive"))
      (node (ref "Q301") (pin "6") (pinfunction "D_6") (pintype "passive"))
      (node (ref "Q301") (pin "7") (pinfunction "D_7") (pintype "passive"))
      (node (ref "Q301") (pin "8") (pinfunction "D_8") (pintype "passive"))
      (node (ref "R300") (pin "1") (pinfunction "1_1") (pintype "passive"))
    )
    (net (code "54") (name "Net-(Q301-G)") (class "Default")
      (node (ref "Q301") (pin "4") (pinfunction "G_4") (pintype "passive"))
      (node (ref "R301") (pin "1") (pinfunction "1_1") (pintype "passive"))
      (node (ref "R320") (pin "1") (pinfunction "1_1") (pintype "passive"))
      (node (ref "R321") (pin "1") (pinfunction "1_1") (pintype "passive"))
    )
    (net (code "55") (name "Net-(Q302-G)") (class "Default")
      (node (ref "Q302") (pin "4") (pinfunction "G_4") (pintype "passive"))
      (node (ref "R303") (pin "2") (pinfunction "2_2") (pintype "passive"))
      (node (ref "R307") (pin "1") (pinfunction "1_1") (pintype "passive"))
    )
    (net (code "56") (name "Net-(Q303-G)") (class "Default")
      (node (ref "Q303") (pin "4") (pinfunction "G_4") (pintype "passive"))
      (node (ref "Q304") (pin "3") (pinfunction "D_3") (pintype "passive"))
      (node (ref "R304") (pin "1") (pinfunction "1_1") (pintype "passive"))
      (node (ref "R308") (pin "1") (pinfunction "1_1") (pintype "passive"))
    )
    (net (code "57") (name "Net-(Q304-G)") (class "Default")
      (node (ref "Q304") (pin "1") (pinfunction "G_1") (pintype "passive"))
      (node (ref "R311") (pin "1") (pinfunction "1_1") (pintype "passive"))
    )
    (net (code "58") (name "Net-(U300-VDD)") (class "Default")
      (node (ref "C310") (pin "1") (pinfunction "1_1") (pintype "passive"))
      (node (ref "R309") (pin "2") (pinfunction "2_2") (pintype "passive"))
      (node (ref "U300") (pin "2") (pinfunction "VDD_2") (pintype "power_in"))
    )
    (net (code "59") (name "Net-(U301-GPOD)") (class "Default")
      (node (ref "R321") (pin "2") (pinfunction "2_2") (pintype "passive"))
      (node (ref "U301") (pin "5") (pinfunction "GPOD_5") (pintype "open_collector"))
    )
    (net (code "60") (name "Net-(U301-PACK)") (class "Default")
      (node (ref "R319") (pin "2") (pinfunction "2_2") (pintype "passive"))
      (node (ref "R322") (pin "2") (pinfunction "2_2") (pintype "passive"))
      (node (ref "U301") (pin "2") (pinfunction "PACK_2") (pintype "passive"))
    )
    (net (code "61") (name "Net-(U301-PMS)") (class "Default")
      (node (ref "R322") (pin "1") (pinfunction "1_1") (pintype "passive"))
      (node (ref "R323") (pin "1") (pinfunction "1_1") (pintype "passive"))
      (node (ref "U301") (pin "6") (pinfunction "PMS_6") (pintype "input"))
    )
    (net (code "62") (name "Net-(U301-RBI)") (class "Default")
      (node (ref "C322") (pin "1") (pinfunction "1_1") (pintype "passive"))
      (node (ref "U301") (pin "33") (pinfunction "RBI_33") (pintype "power_in"))
    )
    (net (code "63") (name "Net-(U301-VCELL+)") (class "Default")
      (node (ref "C320") (pin "1") (pinfunction "1_1") (pintype "passive"))
      (node (ref "U301") (pin "10") (pinfunction "VCELL+_10") (pintype "passive"))
    )
    (net (code "64") (name "Net-(U301-ZVCHG)") (class "Default")
      (node (ref "R320") (pin "2") (pinfunction "2_2") (pintype "passive"))
      (node (ref "U301") (pin "4") (pinfunction "ZVCHG_4") (pintype "output"))
    )
    (net (code "65") (name "Net-(U301-~{MRST})") (class "Default")
      (node (ref "U301") (pin "30") (pinfunction "~{MRST}_30") (pintype "input"))
      (node (ref "U301") (pin "35") (pinfunction "~{RESET}_35") (pintype "output"))
    )
    (net (code "66") (name "unconnected-(P300-Pad4)") (class "Default")
      (node (ref "P300") (pin "4") (pinfunction "4_4") (pintype "passive+no_connect"))
    )
    (net (code "67") (name "unconnected-(U301-SAFE-Pad17)") (class "Default")
      (node (ref "U301") (pin "17") (pinfunction "SAFE_17") (pintype "open_collector"))
    )
    (net (code "68") (name "unconnected-(U301-~{PFIN}-Pad16)") (class "Default")
      (node (ref "U301") (pin "16") (pinfunction "~{PFIN}_16") (pintype "open_collector"))
    )
  )
)
